# helmet_blinker_light_v0_1.net
KiCad netlist of a schematic drawn in EAGLE
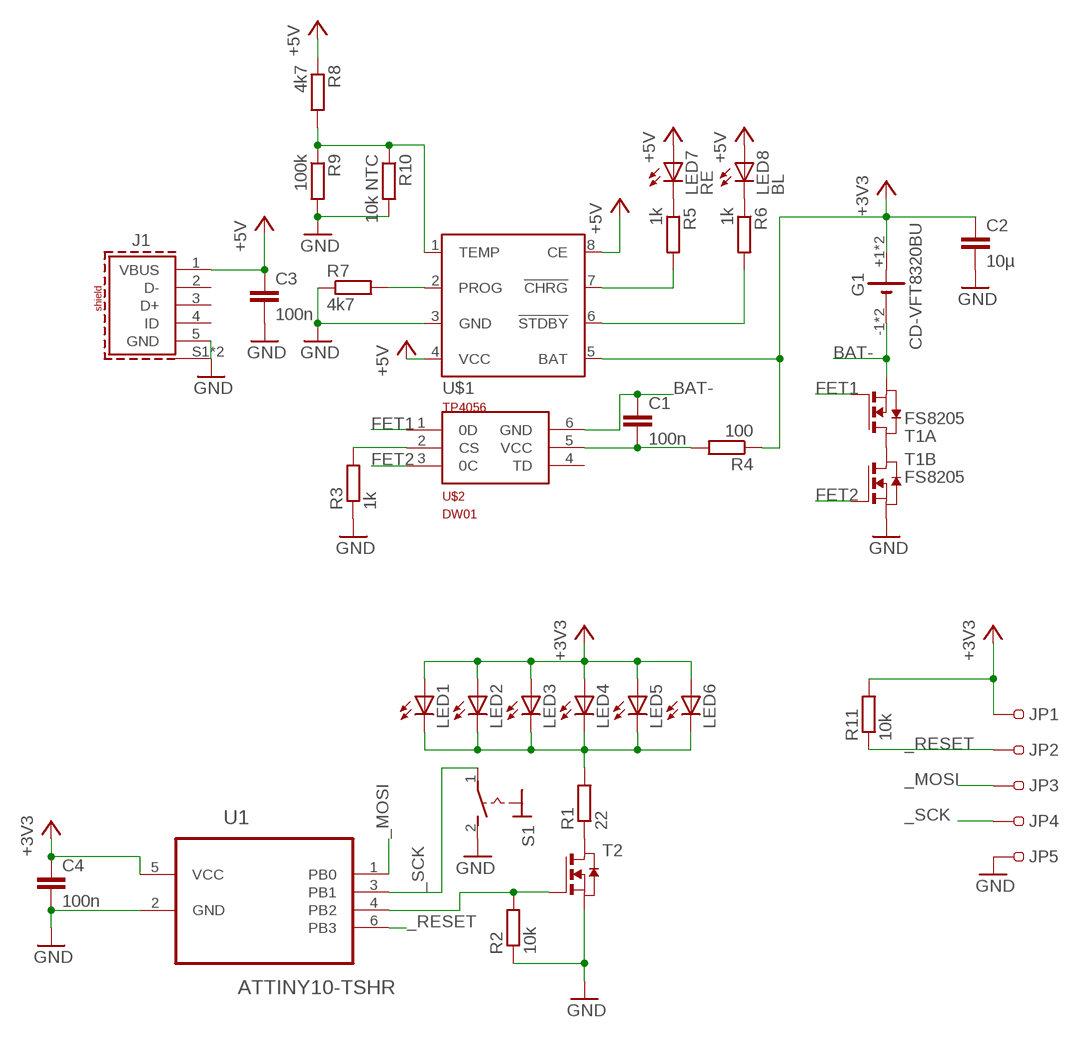
[diagram p0: schematic, sheet 1]

(export (version "E")
  (design (tool "Eeschema 10.0.6"))
  (components
    (comp (ref "C1")
      (value "100n")
      (footprint "eagle-import:C0402K")
      (libsource (lib "eagle-import") (part "C-EUC0402K"))
    )
    (comp (ref "C2")
      (value "10µ")
      (footprint "eagle-import:C0805K")
      (libsource (lib "eagle-import") (part "C-EUC0805K"))
    )
    (comp (ref "C3")
      (value "100n")
      (footprint "eagle-import:C0402K")
      (libsource (lib "eagle-import") (part "C-EUC0402K"))
    )
    (comp (ref "C4")
      (value "100n")
      (footprint "eagle-import:C0402K")
      (libsource (lib "eagle-import") (part "C-EUC0402K"))
    )
    (comp (ref "G1")
      (value "CD-VFT8320BU")
      (footprint "eagle-import:CS-VFT8320BU")
      (libsource (lib "eagle-import") (part "CD-VFT8320BU"))
    )
    (comp (ref "J1")
      (value "614105150621")
      (footprint "eagle-import:614105150621")
      (libsource (lib "eagle-import") (part "614105150621"))
    )
    (comp (ref "JP1")
      (value "0.7MM_POGO-PINS")
      (footprint "eagle-import:0.7MM_POGO-PINS")
      (libsource (lib "eagle-import") (part "0.7MM_POGO-PINS"))
    )
    (comp (ref "JP2")
      (value "0.7MM_POGO-PINS")
      (footprint "eagle-import:0.7MM_POGO-PINS")
      (libsource (lib "eagle-import") (part "0.7MM_POGO-PINS"))
    )
    (comp (ref "JP3")
      (value "0.7MM_POGO-PINS")
      (footprint "eagle-import:0.7MM_POGO-PINS")
      (libsource (lib "eagle-import") (part "0.7MM_POGO-PINS"))
    )
    (comp (ref "JP4")
      (value "0.7MM_POGO-PINS")
      (footprint "eagle-import:0.7MM_POGO-PINS")
      (libsource (lib "eagle-import") (part "0.7MM_POGO-PINS"))
    )
    (comp (ref "JP5")
      (value "0.7MM_POGO-PINS")
      (footprint "eagle-import:0.7MM_POGO-PINS")
      (libsource (lib "eagle-import") (part "0.7MM_POGO-PINS"))
    )
    (comp (ref "LED1")
      (value "LEDCHIPLED_0805")
      (footprint "eagle-import:CHIPLED_0805")
      (libsource (lib "eagle-import") (part "LEDCHIPLED_0805"))
    )
    (comp (ref "LED2")
      (value "LEDCHIPLED_0805")
      (footprint "eagle-import:CHIPLED_0805")
      (libsource (lib "eagle-import") (part "LEDCHIPLED_0805"))
    )
    (comp (ref "LED3")
      (value "LEDCHIPLED_0805")
      (footprint "eagle-import:CHIPLED_0805")
      (libsource (lib "eagle-import") (part "LEDCHIPLED_0805"))
    )
    (comp (ref "LED4")
      (value "LEDCHIPLED_0805")
      (footprint "eagle-import:CHIPLED_0805")
      (libsource (lib "eagle-import") (part "LEDCHIPLED_0805"))
    )
    (comp (ref "LED5")
      (value "LEDCHIPLED_0805")
      (footprint "eagle-import:CHIPLED_0805")
      (libsource (lib "eagle-import") (part "LEDCHIPLED_0805"))
    )
    (comp (ref "LED6")
      (value "LEDCHIPLED_0805")
      (footprint "eagle-import:CHIPLED_0805")
      (libsource (lib "eagle-import") (part "LEDCHIPLED_0805"))
    )
    (comp (ref "LED7")
      (value "RE")
      (footprint "eagle-import:CHIPLED_0805")
      (libsource (lib "eagle-import") (part "LEDCHIPLED_0805"))
    )
    (comp (ref "LED8")
      (value "BL")
      (footprint "eagle-import:CHIPLED_0805")
      (libsource (lib "eagle-import") (part "LEDCHIPLED_0805"))
    )
    (comp (ref "R1")
      (value "22")
      (footprint "eagle-import:R0805")
      (libsource (lib "eagle-import") (part "R-EU_R0805"))
    )
    (comp (ref "R2")
      (value "10k")
      (footprint "eagle-import:R0402")
      (libsource (lib "eagle-import") (part "R-EU_R0402"))
    )
    (comp (ref "R3")
      (value "1k")
      (footprint "eagle-import:R0402")
      (libsource (lib "eagle-import") (part "R-EU_R0402"))
    )
    (comp (ref "R4")
      (value "100")
      (footprint "eagle-import:R0402")
      (libsource (lib "eagle-import") (part "R-EU_R0402"))
    )
    (comp (ref "R5")
      (value "1k")
      (footprint "eagle-import:R0402")
      (libsource (lib "eagle-import") (part "R-EU_R0402"))
    )
    (comp (ref "R6")
      (value "1k")
      (footprint "eagle-import:R0402")
      (libsource (lib "eagle-import") (part "R-EU_R0402"))
    )
    (comp (ref "R7")
      (value "4k7")
      (footprint "eagle-import:R0402")
      (libsource (lib "eagle-import") (part "R-EU_R0402"))
    )
    (comp (ref "R8")
      (value "4k7")
      (footprint "eagle-import:R0402")
      (libsource (lib "eagle-import") (part "R-EU_R0402"))
    )
    (comp (ref "R9")
      (value "100k")
      (footprint "eagle-import:R0402")
      (libsource (lib "eagle-import") (part "R-EU_R0402"))
    )
    (comp (ref "R10")
      (value "10k NTC")
      (footprint "eagle-import:R0805")
      (libsource (lib "eagle-import") (part "R-EU_R0805"))
    )
    (comp (ref "R11")
      (value "10k")
      (footprint "eagle-import:R0402")
      (libsource (lib "eagle-import") (part "R-EU_R0402"))
    )
    (comp (ref "S1")
      (value "TS-1088")
      (footprint "eagle-import:TS-1088")
      (libsource (lib "eagle-import") (part "TS-1088"))
    )
    (comp (ref "T1")
      (value "FS8205")
      (footprint "eagle-import:TSSOP-8")
      (libsource (lib "eagle-import") (part "DMN3024LSD"))
    )
    (comp (ref "T2")
      (value "NMOSSOT23")
      (footprint "eagle-import:SOT-23")
      (libsource (lib "eagle-import") (part "NMOSSOT23"))
    )
    (comp (ref "U$1")
      (value "TP4056")
      (footprint "eagle-import:SOT23-8")
      (libsource (lib "eagle-import") (part "TP4056"))
    )
    (comp (ref "U$2")
      (value "DW01")
      (footprint "eagle-import:SOT23-6")
      (libsource (lib "eagle-import") (part "DW01"))
    )
    (comp (ref "U1")
      (value "ATTINY10-TSHR")
      (footprint "eagle-import:SOT95P280X145-6N")
      (libsource (lib "eagle-import") (part "ATTINY10-TSHR"))
    )
  )
  (nets
    (net (code "1") (name "+3V3") (class "Default")
      (node (ref "C2") (pin "1") (pinfunction "1_1") (pintype "passive"))
      (node (ref "C4") (pin "1") (pinfunction "1_1") (pintype "passive"))
      (node (ref "G1") (pin "+1") (pinfunction "+_+1") (pintype "passive"))
      (node (ref "G1") (pin "+2") (pinfunction "+_+2") (pintype "passive"))
      (node (ref "JP1") (pin "1") (pinfunction "1_1") (pintype "passive"))
      (node (ref "LED1") (pin "A") (pinfunction "A_A") (pintype "passive"))
      (node (ref "LED2") (pin "A") (pinfunction "A_A") (pintype "passive"))
      (node (ref "LED3") (pin "A") (pinfunction "A_A") (pintype "passive"))
      (node (ref "LED4") (pin "A") (pinfunction "A_A") (pintype "passive"))
      (node (ref "LED5") (pin "A") (pinfunction "A_A") (pintype "passive"))
      (node (ref "LED6") (pin "A") (pinfunction "A_A") (pintype "passive"))
      (node (ref "R11") (pin "2") (pinfunction "2_2") (pintype "passive"))
      (node (ref "R4") (pin "1") (pinfunction "1_1") (pintype "passive"))
      (node (ref "U$1") (pin "5") (pinfunction "BAT_5") (pintype "bidirectional"))
      (node (ref "U1") (pin "5") (pinfunction "VCC_5") (pintype "power_in"))
    )
    (net (code "2") (name "+5V") (class "Default")
      (node (ref "C3") (pin "1") (pinfunction "1_1") (pintype "passive"))
      (node (ref "J1") (pin "1") (pinfunction "VBUS_1") (pintype "passive"))
      (node (ref "LED7") (pin "A") (pinfunction "A_A") (pintype "passive"))
      (node (ref "LED8") (pin "A") (pinfunction "A_A") (pintype "passive"))
      (node (ref "R8") (pin "1") (pinfunction "1_1") (pintype "passive"))
      (node (ref "U$1") (pin "4") (pinfunction "VCC_4") (pintype "bidirectional"))
      (node (ref "U$1") (pin "8") (pinfunction "CE_8") (pintype "bidirectional"))
    )
    (net (code "3") (name "/BAT-") (class "Default")
      (node (ref "C1") (pin "1") (pinfunction "1_1") (pintype "passive"))
      (node (ref "G1") (pin "-1") (pinfunction "-_-1") (pintype "passive"))
      (node (ref "G1") (pin "-2") (pinfunction "-_-2") (pintype "passive"))
      (node (ref "T1") (pin "2") (pinfunction "S_2") (pintype "passive"))
      (node (ref "T1") (pin "3") (pinfunction "S_3") (pintype "passive"))
      (node (ref "U$2") (pin "6") (pinfunction "GND_6") (pintype "bidirectional"))
    )
    (net (code "4") (name "/FET1") (class "Default")
      (node (ref "T1") (pin "4") (pinfunction "G_4") (pintype "passive"))
      (node (ref "U$2") (pin "1") (pinfunction "0D_1") (pintype "bidirectional"))
    )
    (net (code "5") (name "/FET2") (class "Default")
      (node (ref "T1") (pin "5") (pinfunction "G_5") (pintype "passive"))
      (node (ref "U$2") (pin "3") (pinfunction "0C_3") (pintype "bidirectional"))
    )
    (net (code "6") (name "/_MOSI") (class "Default")
      (node (ref "JP3") (pin "1") (pinfunction "1_1") (pintype "passive"))
      (node (ref "U1") (pin "1") (pinfunction "PB0_1") (pintype "bidirectional"))
    )
    (net (code "7") (name "/_RESET") (class "Default")
      (node (ref "JP2") (pin "1") (pinfunction "1_1") (pintype "passive"))
      (node (ref "R11") (pin "1") (pinfunction "1_1") (pintype "passive"))
      (node (ref "U1") (pin "6") (pinfunction "PB3_6") (pintype "bidirectional"))
    )
    (net (code "8") (name "/_SCK") (class "Default")
      (node (ref "JP4") (pin "1") (pinfunction "1_1") (pintype "passive"))
      (node (ref "S1") (pin "1") (pinfunction "P_1") (pintype "passive"))
      (node (ref "U1") (pin "3") (pinfunction "PB1_3") (pintype "bidirectional"))
    )
    (net (code "9") (name "GND") (class "Default")
      (node (ref "C2") (pin "2") (pinfunction "2_2") (pintype "passive"))
      (node (ref "C3") (pin "2") (pinfunction "2_2") (pintype "passive"))
      (node (ref "C4") (pin "2") (pinfunction "2_2") (pintype "passive"))
      (node (ref "J1") (pin "5") (pinfunction "GND_5") (pintype "passive"))
      (node (ref "J1") (pin "S1") (pinfunction "SHIELD_S1") (pintype "passive"))
      (node (ref "J1") (pin "S2") (pinfunction "SHIELD_S2") (pintype "passive"))
      (node (ref "JP5") (pin "1") (pinfunction "1_1") (pintype "passive"))
      (node (ref "R10") (pin "2") (pinfunction "2_2") (pintype "passive"))
      (node (ref "R2") (pin "1") (pinfunction "1_1") (pintype "passive"))
      (node (ref "R3") (pin "1") (pinfunction "1_1") (pintype "passive"))
      (node (ref "R7") (pin "1") (pinfunction "1_1") (pintype "passive"))
      (node (ref "R9") (pin "2") (pinfunction "2_2") (pintype "passive"))
      (node (ref "S1") (pin "2") (pinfunction "S_2") (pintype "passive"))
      (node (ref "T1") (pin "6") (pinfunction "S_6") (pintype "passive"))
      (node (ref "T1") (pin "7") (pinfunction "S_7") (pintype "passive"))
      (node (ref "T2") (pin "2") (pinfunction "S_2") (pintype "passive"))
      (node (ref "U$1") (pin "3") (pinfunction "GND_3") (pintype "bidirectional"))
      (node (ref "U1") (pin "2") (pinfunction "GND_2") (pintype "passive"))
    )
    (net (code "10") (name "Net-(LED1-PadC)") (class "Default")
      (node (ref "LED1") (pin "C") (pinfunction "C_C") (pintype "passive"))
      (node (ref "LED2") (pin "C") (pinfunction "C_C") (pintype "passive"))
      (node (ref "LED3") (pin "C") (pinfunction "C_C") (pintype "passive"))
      (node (ref "LED4") (pin "C") (pinfunction "C_C") (pintype "passive"))
      (node (ref "LED5") (pin "C") (pinfunction "C_C") (pintype "passive"))
      (node (ref "LED6") (pin "C") (pinfunction "C_C") (pintype "passive"))
      (node (ref "R1") (pin "2") (pinfunction "2_2") (pintype "passive"))
    )
    (net (code "11") (name "Net-(LED7-PadC)") (class "Default")
      (node (ref "LED7") (pin "C") (pinfunction "C_C") (pintype "passive"))
      (node (ref "R5") (pin "1") (pinfunction "1_1") (pintype "passive"))
    )
    (net (code "12") (name "Net-(LED8-PadC)") (class "Default")
      (node (ref "LED8") (pin "C") (pinfunction "C_C") (pintype "passive"))
      (node (ref "R6") (pin "1") (pinfunction "1_1") (pintype "passive"))
    )
    (net (code "13") (name "Net-(T1A-D)") (class "Default")
      (node (ref "T1") (pin "1") (pinfunction "D_1") (pintype "passive"))
      (node (ref "T1") (pin "8") (pinfunction "D_8") (pintype "passive"))
    )
    (net (code "14") (name "Net-(T2-D)") (class "Default")
      (node (ref "R1") (pin "1") (pinfunction "1_1") (pintype "passive"))
      (node (ref "T2") (pin "1") (pinfunction "D_1") (pintype "passive"))
    )
    (net (code "15") (name "Net-(T2-G)") (class "Default")
      (node (ref "R2") (pin "2") (pinfunction "2_2") (pintype "passive"))
      (node (ref "T2") (pin "3") (pinfunction "G_3") (pintype "passive"))
      (node (ref "U1") (pin "4") (pinfunction "PB2_4") (pintype "bidirectional"))
    )
    (net (code "16") (name "Net-(U$1-PROG)") (class "Default")
      (node (ref "R7") (pin "2") (pinfunction "2_2") (pintype "passive"))
      (node (ref "U$1") (pin "2") (pinfunction "PROG_2") (pintype "bidirectional"))
    )
    (net (code "17") (name "Net-(U$1-TEMP)") (class "Default")
      (node (ref "R10") (pin "1") (pinfunction "1_1") (pintype "passive"))
      (node (ref "R8") (pin "2") (pinfunction "2_2") (pintype "passive"))
      (node (ref "R9") (pin "1") (pinfunction "1_1") (pintype "passive"))
      (node (ref "U$1") (pin "1") (pinfunction "TEMP_1") (pintype "bidirectional"))
    )
    (net (code "18") (name "Net-(U$1-~{CHRG})") (class "Default")
      (node (ref "R5") (pin "2") (pinfunction "2_2") (pintype "passive"))
      (node (ref "U$1") (pin "7") (pinfunction "~{CHRG}_7") (pintype "bidirectional"))
    )
    (net (code "19") (name "Net-(U$1-~{STDBY})") (class "Default")
      (node (ref "R6") (pin "2") (pinfunction "2_2") (pintype "passive"))
      (node (ref "U$1") (pin "6") (pinfunction "~{STDBY}_6") (pintype "bidirectional"))
    )
    (net (code "20") (name "Net-(U$2-CS)") (class "Default")
      (node (ref "R3") (pin "2") (pinfunction "2_2") (pintype "passive"))
      (node (ref "U$2") (pin "2") (pinfunction "CS_2") (pintype "bidirectional"))
    )
    (net (code "21") (name "Net-(U$2-VCC)") (class "Default")
      (node (ref "C1") (pin "2") (pinfunction "2_2") (pintype "passive"))
      (node (ref "R4") (pin "2") (pinfunction "2_2") (pintype "passive"))
      (node (ref "U$2") (pin "5") (pinfunction "VCC_5") (pintype "bidirectional"))
    )
    (net (code "22") (name "unconnected-(J1-D+-Pad3)") (class "Default")
      (node (ref "J1") (pin "3") (pinfunction "D+_3") (pintype "passive"))
    )
    (net (code "23") (name "unconnected-(J1-D--Pad2)") (class "Default")
      (node (ref "J1") (pin "2") (pinfunction "D-_2") (pintype "passive"))
    )
    (net (code "24") (name "unconnected-(J1-ID-Pad4)") (class "Default")
      (node (ref "J1") (pin "4") (pinfunction "ID_4") (pintype "passive"))
    )
    (net (code "25") (name "unconnected-(U$2-TD-Pad4)") (class "Default")
      (node (ref "U$2") (pin "4") (pinfunction "TD_4") (pintype "bidirectional"))
    )
  )
)
